# OSO-FEAL-A1-00.net
KiCad netlist of a schematic drawn in EAGLE
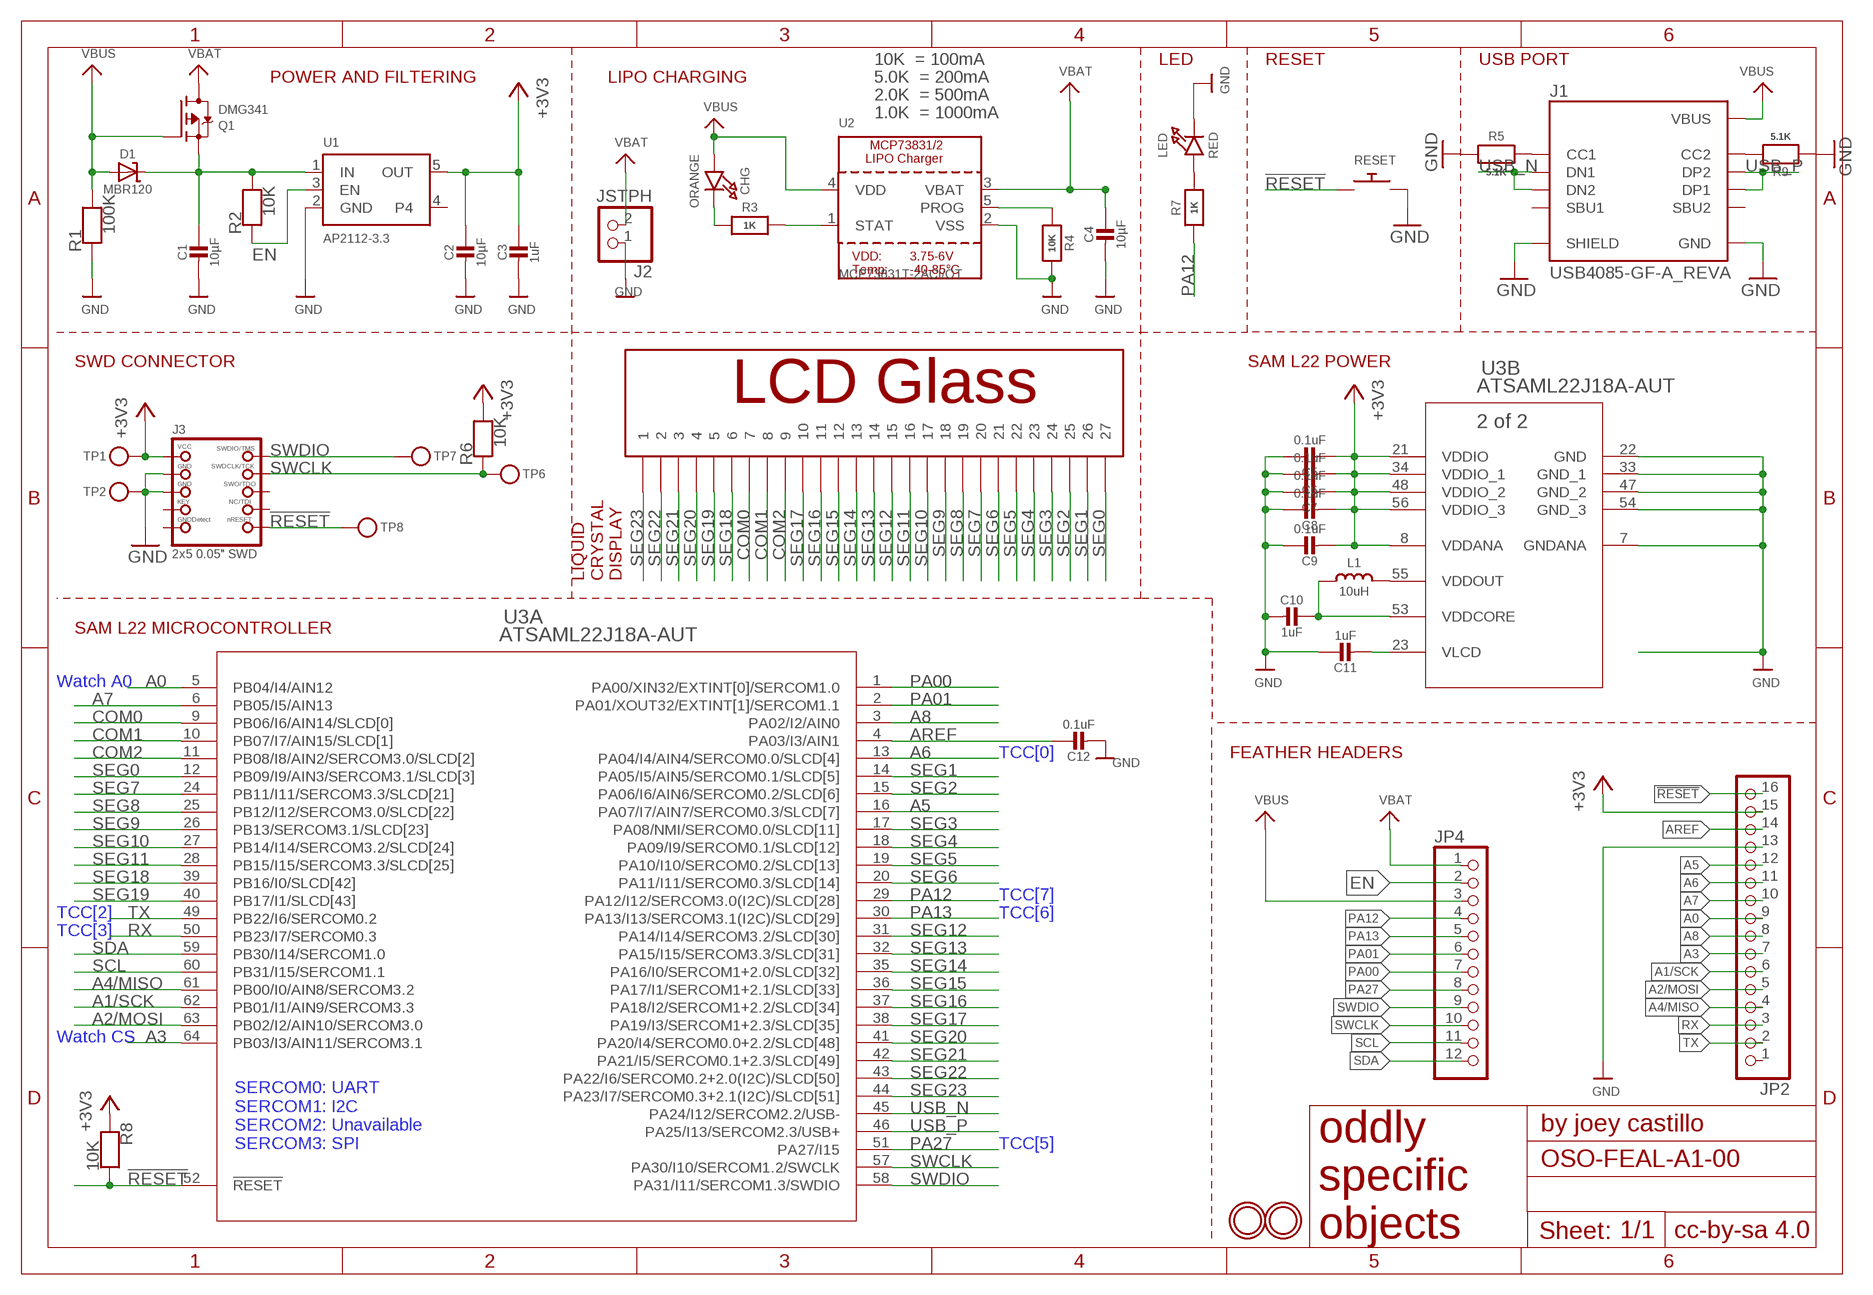
[diagram p0: schematic, sheet 1]

(export (version "E")
  (design (tool "Eeschema 10.0.6"))
  (components
    (comp (ref "C1")
      (value "10µF")
      (footprint "eagle-import:_1206")
      (libsource (lib "eagle-import") (part "CAP_CERAMIC_1206"))
    )
    (comp (ref "C2")
      (value "10µF")
      (footprint "eagle-import:_1206")
      (libsource (lib "eagle-import") (part "CAP_CERAMIC_1206"))
    )
    (comp (ref "C3")
      (value "1uF")
      (footprint "eagle-import:_1206")
      (libsource (lib "eagle-import") (part "CAP_CERAMIC_1206"))
    )
    (comp (ref "C4")
      (value "10µF")
      (footprint "eagle-import:_1206")
      (libsource (lib "eagle-import") (part "CAP_CERAMIC_1206"))
    )
    (comp (ref "C5")
      (value "0.1uF")
      (footprint "eagle-import:0603-NO")
      (libsource (lib "eagle-import") (part "CAP_CERAMIC0603_NO"))
    )
    (comp (ref "C6")
      (value "0.1uF")
      (footprint "eagle-import:0603-NO")
      (libsource (lib "eagle-import") (part "CAP_CERAMIC0603_NO"))
    )
    (comp (ref "C7")
      (value "0.1uF")
      (footprint "eagle-import:0603-NO")
      (libsource (lib "eagle-import") (part "CAP_CERAMIC0603_NO"))
    )
    (comp (ref "C8")
      (value "0.1uF")
      (footprint "eagle-import:0603-NO")
      (libsource (lib "eagle-import") (part "CAP_CERAMIC0603_NO"))
    )
    (comp (ref "C9")
      (value "0.1uF")
      (footprint "eagle-import:0603-NO")
      (libsource (lib "eagle-import") (part "CAP_CERAMIC0603_NO"))
    )
    (comp (ref "C10")
      (value "1uF")
      (footprint "eagle-import:_1206")
      (libsource (lib "eagle-import") (part "CAP_CERAMIC_1206"))
    )
    (comp (ref "C11")
      (value "1uF")
      (footprint "eagle-import:_1206")
      (libsource (lib "eagle-import") (part "CAP_CERAMIC_1206"))
    )
    (comp (ref "C12")
      (value "0.1uF")
      (footprint "eagle-import:0603-NO")
      (libsource (lib "eagle-import") (part "CAP_CERAMIC0603_NO"))
    )
    (comp (ref "CHG")
      (value "ORANGE")
      (footprint "eagle-import:CHIPLED_0805_NOOUTLINE")
      (libsource (lib "eagle-import") (part "LED0805_NOOUTLINE"))
    )
    (comp (ref "D1")
      (value "MBR120")
      (footprint "eagle-import:SOD-123")
      (libsource (lib "eagle-import") (part "DIODE-SCHOTTKYSOD-123"))
    )
    (comp (ref "J1")
      (value "USB4085-GF-A_REVA")
      (footprint "eagle-import:GCT_USB4085-GF-A_REVA")
      (fields
        (field (name "DIGI-KEY_PART_NUMBER") "2073-USB4085-GF-ACT-ND")
        (field (name "MF") "Global Connector Technology")
        (field (name "MP") "USB4085-GF-A")
      )
      (libsource (lib "eagle-import") (part "USB4085-GF-A_REVA"))
    )
    (comp (ref "J2")
      (value "JSTPH")
      (footprint "eagle-import:JSTPH2")
      (libsource (lib "eagle-import") (part "CON_JST_PH_2PIN"))
    )
    (comp (ref "J3")
      (value "2x5 0.05\" SWD")
      (footprint "eagle-import:2X05_1.27MM_BOX_NOPOSTS")
      (libsource (lib "eagle-import") (part "JTAG-CORTEXBOX"))
    )
    (comp (ref "JP2")
      (value "HEADER-1X16_MIN")
      (footprint "eagle-import:1X16_ROUND_MIN")
      (libsource (lib "eagle-import") (part "HEADER-1X16_MIN"))
    )
    (comp (ref "JP4")
      (value "HEADER-1X12_MIN")
      (footprint "eagle-import:1X12_ROUND_MIN")
      (libsource (lib "eagle-import") (part "HEADER-1X12_MIN"))
    )
    (comp (ref "L1")
      (value "10uH")
      (footprint "eagle-import:MICROBUILDER__0805MP")
      (libsource (lib "eagle-import") (part "MICROBUILDER_INDUCTOR_0805MP"))
    )
    (comp (ref "LED")
      (value "RED")
      (footprint "eagle-import:CHIPLED_0805_NOOUTLINE")
      (libsource (lib "eagle-import") (part "LED0805_NOOUTLINE"))
    )
    (comp (ref "Q1")
      (value "DMG341")
      (footprint "eagle-import:SOT23-R")
      (libsource (lib "eagle-import") (part "MOSFET-P"))
    )
    (comp (ref "R1")
      (value "100K")
      (footprint "eagle-import:0603-NO")
      (libsource (lib "eagle-import") (part "RESISTOR_0603_NOOUT"))
    )
    (comp (ref "R2")
      (value "10K")
      (footprint "eagle-import:0603-NO")
      (libsource (lib "eagle-import") (part "RESISTOR_0603_NOOUT"))
    )
    (comp (ref "R3")
      (value "1K")
      (footprint "eagle-import:0603-NO")
      (libsource (lib "eagle-import") (part "RESISTOR_0603_NOOUT"))
    )
    (comp (ref "R4")
      (value "10K")
      (footprint "eagle-import:0603-NO")
      (libsource (lib "eagle-import") (part "RESISTOR_0603_NOOUT"))
    )
    (comp (ref "R5")
      (value "5.1K")
      (footprint "eagle-import:0603-NO")
      (libsource (lib "eagle-import") (part "RESISTOR_0603_NOOUT"))
    )
    (comp (ref "R6")
      (value "10K")
      (footprint "eagle-import:0603-NO")
      (libsource (lib "eagle-import") (part "RESISTOR_0603_NOOUT"))
    )
    (comp (ref "R7")
      (value "1K")
      (footprint "eagle-import:0603-NO")
      (libsource (lib "eagle-import") (part "RESISTOR_0603_NOOUT"))
    )
    (comp (ref "R8")
      (value "10K")
      (footprint "eagle-import:0603-NO")
      (libsource (lib "eagle-import") (part "RESISTOR_0603_NOOUT"))
    )
    (comp (ref "R9")
      (value "5.1K")
      (footprint "eagle-import:0603-NO")
      (libsource (lib "eagle-import") (part "RESISTOR_0603_NOOUT"))
    )
    (comp (ref "RESET")
      (value "SWITCH_PUSHBUTTON_3.5X6MM")
      (footprint "eagle-import:TACTILE_3X6MM")
      (libsource (lib "eagle-import") (part "SWITCH_PUSHBUTTON_3.5X6MM"))
    )
    (comp (ref "TP1")
      (value "TESTPOINTROUND2MMNO")
      (footprint "eagle-import:TESTPOINT_ROUND_2MM_NO")
      (libsource (lib "eagle-import") (part "TESTPOINTROUND2MMNO"))
    )
    (comp (ref "TP2")
      (value "TESTPOINTROUND2MMNO")
      (footprint "eagle-import:TESTPOINT_ROUND_2MM_NO")
      (libsource (lib "eagle-import") (part "TESTPOINTROUND2MMNO"))
    )
    (comp (ref "TP6")
      (value "TESTPOINTROUND2MMNO")
      (footprint "eagle-import:TESTPOINT_ROUND_2MM_NO")
      (libsource (lib "eagle-import") (part "TESTPOINTROUND2MMNO"))
    )
    (comp (ref "TP7")
      (value "TESTPOINTROUND2MMNO")
      (footprint "eagle-import:TESTPOINT_ROUND_2MM_NO")
      (libsource (lib "eagle-import") (part "TESTPOINTROUND2MMNO"))
    )
    (comp (ref "TP8")
      (value "TESTPOINTROUND2MMNO")
      (footprint "eagle-import:TESTPOINT_ROUND_2MM_NO")
      (libsource (lib "eagle-import") (part "TESTPOINTROUND2MMNO"))
    )
    (comp (ref "U$4")
      (value "LCD_FEATHER_DISPLAY")
      (footprint "eagle-import:LCD_FEATHER_DISPLAY")
      (libsource (lib "eagle-import") (part "LCD_FEATHER_DISPLAY"))
    )
    (comp (ref "U$31")
      (value "MOUNTINGHOLE2.5")
      (footprint "eagle-import:MOUNTINGHOLE_2.5_PLATED")
      (libsource (lib "eagle-import") (part "MOUNTINGHOLE2.5"))
    )
    (comp (ref "U$32")
      (value "MOUNTINGHOLE2.5")
      (footprint "eagle-import:MOUNTINGHOLE_2.5_PLATED")
      (libsource (lib "eagle-import") (part "MOUNTINGHOLE2.5"))
    )
    (comp (ref "U1")
      (value "AP2112-3.3")
      (footprint "eagle-import:SOT23-5")
      (libsource (lib "eagle-import") (part "VREG_SOT23-5"))
    )
    (comp (ref "U2")
      (value "MCP73831T-2ACI/OT")
      (footprint "eagle-import:SOT23-5")
      (libsource (lib "eagle-import") (part "MCP73831/2"))
    )
    (comp (ref "U3")
      (value "ATSAML22J18A-AUT")
      (footprint "eagle-import:TQFP64_10X10MC_MCH-L")
      (libsource (lib "eagle-import") (part "ATSAML22J18A-AUT"))
    )
  )
  (nets
    (net (code "1") (name "+3V3") (class "Default")
      (node (ref "C2") (pin "1") (pinfunction "1_1") (pintype "passive"))
      (node (ref "C3") (pin "1") (pinfunction "1_1") (pintype "passive"))
      (node (ref "C5") (pin "2") (pinfunction "2_2") (pintype "passive"))
      (node (ref "C6") (pin "2") (pinfunction "2_2") (pintype "passive"))
      (node (ref "C7") (pin "2") (pinfunction "2_2") (pintype "passive"))
      (node (ref "C8") (pin "2") (pinfunction "2_2") (pintype "passive"))
      (node (ref "C9") (pin "2") (pinfunction "2_2") (pintype "passive"))
      (node (ref "J3") (pin "1") (pinfunction "VCC_1") (pintype "power_in"))
      (node (ref "JP2") (pin "15") (pinfunction "15_15") (pintype "passive"))
      (node (ref "R6") (pin "2") (pinfunction "2_2") (pintype "passive"))
      (node (ref "R8") (pin "1") (pinfunction "1_1") (pintype "passive"))
      (node (ref "TP1") (pin "P$1") (pinfunction "P$1_P$1") (pintype "bidirectional"))
      (node (ref "U1") (pin "5") (pinfunction "OUT_5") (pintype "power_in"))
      (node (ref "U3") (pin "21") (pinfunction "VDDIO_21") (pintype "power_in"))
      (node (ref "U3") (pin "34") (pinfunction "VDDIO_1_34") (pintype "power_in"))
      (node (ref "U3") (pin "48") (pinfunction "VDDIO_2_48") (pintype "power_in"))
      (node (ref "U3") (pin "56") (pinfunction "VDDIO_3_56") (pintype "power_in"))
      (node (ref "U3") (pin "8") (pinfunction "VDDANA_8") (pintype "power_in"))
    )
    (net (code "2") (name "/COM0") (class "Default")
      (node (ref "U$4") (pin "P$7") (pinfunction "7_P$7") (pintype "input"))
      (node (ref "U3") (pin "9") (pinfunction "PB06/I6/AIN14/SLCD[0]_9") (pintype "bidirectional"))
    )
    (net (code "3") (name "/COM1") (class "Default")
      (node (ref "U$4") (pin "P$8") (pinfunction "8_P$8") (pintype "input"))
      (node (ref "U3") (pin "10") (pinfunction "PB07/I7/AIN15/SLCD[1]_10") (pintype "bidirectional"))
    )
    (net (code "4") (name "/COM2") (class "Default")
      (node (ref "U$4") (pin "P$9") (pinfunction "9_P$9") (pintype "input"))
      (node (ref "U3") (pin "11") (pinfunction "PB08/I8/AIN2/SERCOM3.0/SLCD[2]_11") (pintype "bidirectional"))
    )
    (net (code "5") (name "/SEG0") (class "Default")
      (node (ref "U$4") (pin "P$27") (pinfunction "27_P$27") (pintype "input"))
      (node (ref "U3") (pin "12") (pinfunction "PB09/I9/AIN3/SERCOM3.1/SLCD[3]_12") (pintype "bidirectional"))
    )
    (net (code "6") (name "/SEG1") (class "Default")
      (node (ref "U$4") (pin "P$26") (pinfunction "26_P$26") (pintype "input"))
      (node (ref "U3") (pin "14") (pinfunction "PA05/I5/AIN5/SERCOM0.1/SLCD[5]_14") (pintype "bidirectional"))
    )
    (net (code "7") (name "/SEG2") (class "Default")
      (node (ref "U$4") (pin "P$25") (pinfunction "25_P$25") (pintype "input"))
      (node (ref "U3") (pin "15") (pinfunction "PA06/I6/AIN6/SERCOM0.2/SLCD[6]_15") (pintype "bidirectional"))
    )
    (net (code "8") (name "/SEG3") (class "Default")
      (node (ref "U$4") (pin "P$24") (pinfunction "24_P$24") (pintype "input"))
      (node (ref "U3") (pin "17") (pinfunction "PA08/NMI/SERCOM0.0/SLCD[11]_17") (pintype "bidirectional"))
    )
    (net (code "9") (name "/SEG4") (class "Default")
      (node (ref "U$4") (pin "P$23") (pinfunction "23_P$23") (pintype "input"))
      (node (ref "U3") (pin "18") (pinfunction "PA09/I9/SERCOM0.1/SLCD[12]_18") (pintype "bidirectional"))
    )
    (net (code "10") (name "/SEG5") (class "Default")
      (node (ref "U$4") (pin "P$22") (pinfunction "22_P$22") (pintype "input"))
      (node (ref "U3") (pin "19") (pinfunction "PA10/I10/SERCOM0.2/SLCD[13]_19") (pintype "bidirectional"))
    )
    (net (code "11") (name "/SEG6") (class "Default")
      (node (ref "U$4") (pin "P$21") (pinfunction "21_P$21") (pintype "input"))
      (node (ref "U3") (pin "20") (pinfunction "PA11/I11/SERCOM0.3/SLCD[14]_20") (pintype "bidirectional"))
    )
    (net (code "12") (name "/SEG7") (class "Default")
      (node (ref "U$4") (pin "P$20") (pinfunction "20_P$20") (pintype "input"))
      (node (ref "U3") (pin "24") (pinfunction "PB11/I11/SERCOM3.3/SLCD[21]_24") (pintype "bidirectional"))
    )
    (net (code "13") (name "/SEG8") (class "Default")
      (node (ref "U$4") (pin "P$19") (pinfunction "19_P$19") (pintype "input"))
      (node (ref "U3") (pin "25") (pinfunction "PB12/I12/SERCOM3.0/SLCD[22]_25") (pintype "bidirectional"))
    )
    (net (code "14") (name "/SEG9") (class "Default")
      (node (ref "U$4") (pin "P$18") (pinfunction "18_P$18") (pintype "input"))
      (node (ref "U3") (pin "26") (pinfunction "PB13/SERCOM3.1/SLCD[23]_26") (pintype "bidirectional"))
    )
    (net (code "15") (name "/SEG10") (class "Default")
      (node (ref "U$4") (pin "P$17") (pinfunction "17_P$17") (pintype "input"))
      (node (ref "U3") (pin "27") (pinfunction "PB14/I14/SERCOM3.2/SLCD[24]_27") (pintype "bidirectional"))
    )
    (net (code "16") (name "/SEG11") (class "Default")
      (node (ref "U$4") (pin "P$16") (pinfunction "16_P$16") (pintype "input"))
      (node (ref "U3") (pin "28") (pinfunction "PB15/I15/SERCOM3.3/SLCD[25]_28") (pintype "bidirectional"))
    )
    (net (code "17") (name "/SEG12") (class "Default")
      (node (ref "U$4") (pin "P$15") (pinfunction "15_P$15") (pintype "input"))
      (node (ref "U3") (pin "31") (pinfunction "PA14/I14/SERCOM3.2/SLCD[30]_31") (pintype "bidirectional"))
    )
    (net (code "18") (name "/SEG13") (class "Default")
      (node (ref "U$4") (pin "P$14") (pinfunction "14_P$14") (pintype "input"))
      (node (ref "U3") (pin "32") (pinfunction "PA15/I15/SERCOM3.3/SLCD[31]_32") (pintype "bidirectional"))
    )
    (net (code "19") (name "/SEG14") (class "Default")
      (node (ref "U$4") (pin "P$13") (pinfunction "13_P$13") (pintype "input"))
      (node (ref "U3") (pin "35") (pinfunction "PA16/I0/SERCOM1+2.0/SLCD[32]_35") (pintype "bidirectional"))
    )
    (net (code "20") (name "/SEG15") (class "Default")
      (node (ref "U$4") (pin "P$12") (pinfunction "12_P$12") (pintype "input"))
      (node (ref "U3") (pin "36") (pinfunction "PA17/I1/SERCOM1+2.1/SLCD[33]_36") (pintype "bidirectional"))
    )
    (net (code "21") (name "/SEG16") (class "Default")
      (node (ref "U$4") (pin "P$11") (pinfunction "11_P$11") (pintype "input"))
      (node (ref "U3") (pin "37") (pinfunction "PA18/I2/SERCOM1+2.2/SLCD[34]_37") (pintype "bidirectional"))
    )
    (net (code "22") (name "/SEG17") (class "Default")
      (node (ref "U$4") (pin "P$10") (pinfunction "10_P$10") (pintype "input"))
      (node (ref "U3") (pin "38") (pinfunction "PA19/I3/SERCOM1+2.3/SLCD[35]_38") (pintype "bidirectional"))
    )
    (net (code "23") (name "/SEG18") (class "Default")
      (node (ref "U$4") (pin "P$6") (pinfunction "6_P$6") (pintype "input"))
      (node (ref "U3") (pin "39") (pinfunction "PB16/I0/SLCD[42]_39") (pintype "bidirectional"))
    )
    (net (code "24") (name "/SEG19") (class "Default")
      (node (ref "U$4") (pin "P$5") (pinfunction "5_P$5") (pintype "input"))
      (node (ref "U3") (pin "40") (pinfunction "PB17/I1/SLCD[43]_40") (pintype "bidirectional"))
    )
    (net (code "25") (name "/SEG20") (class "Default")
      (node (ref "U$4") (pin "P$4") (pinfunction "4_P$4") (pintype "input"))
      (node (ref "U3") (pin "41") (pinfunction "PA20/I4/SERCOM0.0+2.2/SLCD[48]_41") (pintype "bidirectional"))
    )
    (net (code "26") (name "/SEG21") (class "Default")
      (node (ref "U$4") (pin "P$3") (pinfunction "3_P$3") (pintype "input"))
      (node (ref "U3") (pin "42") (pinfunction "PA21/I5/SERCOM0.1+2.3/SLCD[49]_42") (pintype "bidirectional"))
    )
    (net (code "27") (name "/SEG22") (class "Default")
      (node (ref "U$4") (pin "P$2") (pinfunction "2_P$2") (pintype "input"))
      (node (ref "U3") (pin "43") (pinfunction "PA22/I6/SERCOM0.2+2.0(I2C)/SLCD[50]_43") (pintype "bidirectional"))
    )
    (net (code "28") (name "/SEG23") (class "Default")
      (node (ref "U$4") (pin "P$1") (pinfunction "1_P$1") (pintype "input"))
      (node (ref "U3") (pin "44") (pinfunction "PA23/I7/SERCOM0.3+2.1(I2C)/SLCD[51]_44") (pintype "bidirectional"))
    )
    (net (code "29") (name "/USB_N") (class "Default")
      (node (ref "J1") (pin "A7") (pinfunction "DN1_A7") (pintype "bidirectional"))
      (node (ref "J1") (pin "B7") (pinfunction "DN2_B7") (pintype "bidirectional"))
      (node (ref "U3") (pin "45") (pinfunction "PA24/I12/SERCOM2.2/USB-_45") (pintype "bidirectional"))
    )
    (net (code "30") (name "/USB_P") (class "Default")
      (node (ref "J1") (pin "A6") (pinfunction "DP1_A6") (pintype "bidirectional"))
      (node (ref "J1") (pin "B6") (pinfunction "DP2_B6") (pintype "bidirectional"))
      (node (ref "U3") (pin "46") (pinfunction "PA25/I13/SERCOM2.3/USB+_46") (pintype "bidirectional"))
    )
    (net (code "31") (name "/~{RESET}") (class "Default")
      (node (ref "J3") (pin "10") (pinfunction "NRESET_10") (pintype "bidirectional"))
      (node (ref "JP2") (pin "16") (pinfunction "16_16") (pintype "passive"))
      (node (ref "R8") (pin "2") (pinfunction "2_2") (pintype "passive"))
      (node (ref "RESET") (pin "P$1") (pinfunction "P$1_P$1") (pintype "passive"))
      (node (ref "TP8") (pin "P$1") (pinfunction "P$1_P$1") (pintype "bidirectional"))
      (node (ref "U3") (pin "52") (pinfunction "~{RESET}_52") (pintype "bidirectional"))
    )
    (net (code "32") (name "A0") (class "Default")
      (node (ref "JP2") (pin "9") (pinfunction "9_9") (pintype "passive"))
      (node (ref "U3") (pin "5") (pinfunction "PB04/I4/AIN12_5") (pintype "bidirectional"))
    )
    (net (code "33") (name "A1{slash}SCK") (class "Default")
      (node (ref "JP2") (pin "6") (pinfunction "6_6") (pintype "passive"))
      (node (ref "U3") (pin "62") (pinfunction "PB01/I1/AIN9/SERCOM3.3_62") (pintype "bidirectional"))
    )
    (net (code "34") (name "A2{slash}MOSI") (class "Default")
      (node (ref "JP2") (pin "5") (pinfunction "5_5") (pintype "passive"))
      (node (ref "U3") (pin "63") (pinfunction "PB02/I2/AIN10/SERCOM3.0_63") (pintype "bidirectional"))
    )
    (net (code "35") (name "A3") (class "Default")
      (node (ref "JP2") (pin "7") (pinfunction "7_7") (pintype "passive"))
      (node (ref "U3") (pin "64") (pinfunction "PB03/I3/AIN11/SERCOM3.1_64") (pintype "bidirectional"))
    )
    (net (code "36") (name "A4{slash}MISO") (class "Default")
      (node (ref "JP2") (pin "4") (pinfunction "4_4") (pintype "passive"))
      (node (ref "U3") (pin "61") (pinfunction "PB00/I0/AIN8/SERCOM3.2_61") (pintype "bidirectional"))
    )
    (net (code "37") (name "A5") (class "Default")
      (node (ref "JP2") (pin "12") (pinfunction "12_12") (pintype "passive"))
      (node (ref "U3") (pin "16") (pinfunction "PA07/I7/AIN7/SERCOM0.3/SLCD[7]_16") (pintype "bidirectional"))
    )
    (net (code "38") (name "A6") (class "Default")
      (node (ref "JP2") (pin "11") (pinfunction "11_11") (pintype "passive"))
      (node (ref "U3") (pin "13") (pinfunction "PA04/I4/AIN4/SERCOM0.0/SLCD[4]_13") (pintype "bidirectional"))
    )
    (net (code "39") (name "A7") (class "Default")
      (node (ref "JP2") (pin "10") (pinfunction "10_10") (pintype "passive"))
      (node (ref "U3") (pin "6") (pinfunction "PB05/I5/AIN13_6") (pintype "bidirectional"))
    )
    (net (code "40") (name "A8") (class "Default")
      (node (ref "JP2") (pin "8") (pinfunction "8_8") (pintype "passive"))
      (node (ref "U3") (pin "3") (pinfunction "PA02/I2/AIN0_3") (pintype "bidirectional"))
    )
    (net (code "41") (name "AREF") (class "Default")
      (node (ref "C12") (pin "1") (pinfunction "1_1") (pintype "passive"))
      (node (ref "JP2") (pin "14") (pinfunction "14_14") (pintype "passive"))
      (node (ref "U3") (pin "4") (pinfunction "PA03/I3/AIN1_4") (pintype "bidirectional"))
    )
    (net (code "42") (name "EN") (class "Default")
      (node (ref "JP4") (pin "2") (pinfunction "2_2") (pintype "passive"))
      (node (ref "R2") (pin "1") (pinfunction "1_1") (pintype "passive"))
      (node (ref "U1") (pin "3") (pinfunction "EN_3") (pintype "input"))
    )
    (net (code "43") (name "GND") (class "Default")
      (node (ref "C1") (pin "2") (pinfunction "2_2") (pintype "passive"))
      (node (ref "C10") (pin "2") (pinfunction "2_2") (pintype "passive"))
      (node (ref "C11") (pin "1") (pinfunction "1_1") (pintype "passive"))
      (node (ref "C12") (pin "2") (pinfunction "2_2") (pintype "passive"))
      (node (ref "C2") (pin "2") (pinfunction "2_2") (pintype "passive"))
      (node (ref "C3") (pin "2") (pinfunction "2_2") (pintype "passive"))
      (node (ref "C4") (pin "2") (pinfunction "2_2") (pintype "passive"))
      (node (ref "C5") (pin "1") (pinfunction "1_1") (pintype "passive"))
      (node (ref "C6") (pin "1") (pinfunction "1_1") (pintype "passive"))
      (node (ref "C7") (pin "1") (pinfunction "1_1") (pintype "passive"))
      (node (ref "C8") (pin "1") (pinfunction "1_1") (pintype "passive"))
      (node (ref "C9") (pin "1") (pinfunction "1_1") (pintype "passive"))
      (node (ref "J1") (pin "A1") (pinfunction "GND_A1") (pintype "passive"))
      (node (ref "J1") (pin "A12") (pinfunction "GND_A12") (pintype "passive"))
      (node (ref "J1") (pin "B1") (pinfunction "GND_B1") (pintype "passive"))
      (node (ref "J1") (pin "B12") (pinfunction "GND_B12") (pintype "passive"))
      (node (ref "J1") (pin "P1") (pinfunction "SHIELD_P1") (pintype "passive"))
      (node (ref "J1") (pin "P2") (pinfunction "SHIELD_P2") (pintype "passive"))
      (node (ref "J1") (pin "P3") (pinfunction "SHIELD_P3") (pintype "passive"))
      (node (ref "J1") (pin "P4") (pinfunction "SHIELD_P4") (pintype "passive"))
      (node (ref "J2") (pin "1") (pinfunction "1_1") (pintype "passive"))
      (node (ref "J3") (pin "3") (pinfunction "GND_3") (pintype "power_in"))
      (node (ref "J3") (pin "5") (pinfunction "GND_5") (pintype "power_in"))
      (node (ref "JP2") (pin "13") (pinfunction "13_13") (pintype "passive"))
      (node (ref "LED") (pin "C") (pinfunction "C_C") (pintype "passive"))
      (node (ref "R1") (pin "1") (pinfunction "1_1") (pintype "passive"))
      (node (ref "R4") (pin "2") (pinfunction "2_2") (pintype "passive"))
      (node (ref "R5") (pin "1") (pinfunction "1_1") (pintype "passive"))
      (node (ref "R9") (pin "2") (pinfunction "2_2") (pintype "passive"))
      (node (ref "RESET") (pin "P$2") (pinfunction "P$2_P$2") (pintype "passive"))
      (node (ref "TP2") (pin "P$1") (pinfunction "P$1_P$1") (pintype "bidirectional"))
      (node (ref "U1") (pin "2") (pinfunction "GND_2") (pintype "power_in"))
      (node (ref "U2") (pin "2") (pinfunction "VSS_2") (pintype "power_in"))
      (node (ref "U3") (pin "22") (pinfunction "GND_22") (pintype "passive"))
      (node (ref "U3") (pin "33") (pinfunction "GND_1_33") (pintype "passive"))
      (node (ref "U3") (pin "47") (pinfunction "GND_2_47") (pintype "passive"))
      (node (ref "U3") (pin "54") (pinfunction "GND_3_54") (pintype "passive"))
      (node (ref "U3") (pin "7") (pinfunction "GNDANA_7") (pintype "passive"))
    )
    (net (code "44") (name "Net-(CHG-PadC)") (class "Default")
      (node (ref "CHG") (pin "C") (pinfunction "C_C") (pintype "passive"))
      (node (ref "R3") (pin "1") (pinfunction "1_1") (pintype "passive"))
    )
    (net (code "45") (name "Net-(J1-CC1)") (class "Default")
      (node (ref "J1") (pin "A5") (pinfunction "CC1_A5") (pintype "bidirectional"))
      (node (ref "R5") (pin "2") (pinfunction "2_2") (pintype "passive"))
    )
    (net (code "46") (name "Net-(J1-CC2)") (class "Default")
      (node (ref "J1") (pin "B5") (pinfunction "CC2_B5") (pintype "bidirectional"))
      (node (ref "R9") (pin "1") (pinfunction "1_1") (pintype "passive"))
    )
    (net (code "47") (name "Net-(LED-PadA)") (class "Default")
      (node (ref "LED") (pin "A") (pinfunction "A_A") (pintype "passive"))
      (node (ref "R7") (pin "2") (pinfunction "2_2") (pintype "passive"))
    )
    (net (code "48") (name "Net-(Q1-S)") (class "Default")
      (node (ref "C1") (pin "1") (pinfunction "1_1") (pintype "passive"))
      (node (ref "D1") (pin "C") (pinfunction "C_C") (pintype "passive"))
      (node (ref "Q1") (pin "2") (pinfunction "S_2") (pintype "passive"))
      (node (ref "R2") (pin "2") (pinfunction "2_2") (pintype "passive"))
      (node (ref "U1") (pin "1") (pinfunction "IN_1") (pintype "power_in"))
    )
    (net (code "49") (name "Net-(U2-PROG)") (class "Default")
      (node (ref "R4") (pin "1") (pinfunction "1_1") (pintype "passive"))
      (node (ref "U2") (pin "5") (pinfunction "PROG_5") (pintype "input"))
    )
    (net (code "50") (name "Net-(U2-STAT)") (class "Default")
      (node (ref "R3") (pin "2") (pinfunction "2_2") (pintype "passive"))
      (node (ref "U2") (pin "1") (pinfunction "STAT_1") (pintype "output"))
    )
    (net (code "51") (name "Net-(U3B-VDDCORE)") (class "Default")
      (node (ref "C10") (pin "1") (pinfunction "1_1") (pintype "passive"))
      (node (ref "L1") (pin "1") (pinfunction "1_1") (pintype "passive"))
      (node (ref "U3") (pin "53") (pinfunction "VDDCORE_53") (pintype "power_in"))
    )
    (net (code "52") (name "Net-(U3B-VDDOUT)") (class "Default")
      (node (ref "L1") (pin "2") (pinfunction "2_2") (pintype "passive"))
      (node (ref "U3") (pin "55") (pinfunction "VDDOUT_55") (pintype "output"))
    )
    (net (code "53") (name "Net-(U3B-VLCD)") (class "Default")
      (node (ref "C11") (pin "2") (pinfunction "2_2") (pintype "passive"))
      (node (ref "U3") (pin "23") (pinfunction "VLCD_23") (pintype "passive"))
    )
    (net (code "54") (name "PA00") (class "Default")
      (node (ref "JP4") (pin "7") (pinfunction "7_7") (pintype "passive"))
      (node (ref "U3") (pin "1") (pinfunction "PA00/XIN32/EXTINT[0]/SERCOM1.0_1") (pintype "bidirectional"))
    )
    (net (code "55") (name "PA01") (class "Default")
      (node (ref "JP4") (pin "6") (pinfunction "6_6") (pintype "passive"))
      (node (ref "U3") (pin "2") (pinfunction "PA01/XOUT32/EXTINT[1]/SERCOM1.1_2") (pintype "bidirectional"))
    )
    (net (code "56") (name "PA12") (class "Default")
      (node (ref "JP4") (pin "4") (pinfunction "4_4") (pintype "passive"))
      (node (ref "R7") (pin "1") (pinfunction "1_1") (pintype "passive"))
      (node (ref "U3") (pin "29") (pinfunction "PA12/I12/SERCOM3.0(I2C)/SLCD[28]_29") (pintype "bidirectional"))
    )
    (net (code "57") (name "PA13") (class "Default")
      (node (ref "JP4") (pin "5") (pinfunction "5_5") (pintype "passive"))
      (node (ref "U3") (pin "30") (pinfunction "PA13/I13/SERCOM3.1(I2C)/SLCD[29]_30") (pintype "bidirectional"))
    )
    (net (code "58") (name "PA27") (class "Default")
      (node (ref "JP4") (pin "8") (pinfunction "8_8") (pintype "passive"))
      (node (ref "U3") (pin "51") (pinfunction "PA27/I15_51") (pintype "bidirectional"))
    )
    (net (code "59") (name "RX") (class "Default")
      (node (ref "JP2") (pin "3") (pinfunction "3_3") (pintype "passive"))
      (node (ref "U3") (pin "50") (pinfunction "PB23/I7/SERCOM0.3_50") (pintype "bidirectional"))
    )
    (net (code "60") (name "SCL") (class "Default")
      (node (ref "JP4") (pin "11") (pinfunction "11_11") (pintype "passive"))
      (node (ref "U3") (pin "60") (pinfunction "PB31/I15/SERCOM1.1_60") (pintype "bidirectional"))
    )
    (net (code "61") (name "SDA") (class "Default")
      (node (ref "JP4") (pin "12") (pinfunction "12_12") (pintype "passive"))
      (node (ref "U3") (pin "59") (pinfunction "PB30/I14/SERCOM1.0_59") (pintype "bidirectional"))
    )
    (net (code "62") (name "SWCLK") (class "Default")
      (node (ref "J3") (pin "4") (pinfunction "SWDCLK_4") (pintype "bidirectional"))
      (node (ref "JP4") (pin "10") (pinfunction "10_10") (pintype "passive"))
      (node (ref "R6") (pin "1") (pinfunction "1_1") (pintype "passive"))
      (node (ref "TP6") (pin "P$1") (pinfunction "P$1_P$1") (pintype "bidirectional"))
      (node (ref "U3") (pin "57") (pinfunction "PA30/I10/SERCOM1.2/SWCLK_57") (pintype "bidirectional"))
    )
    (net (code "63") (name "SWDIO") (class "Default")
      (node (ref "J3") (pin "2") (pinfunction "SWDIO_2") (pintype "bidirectional"))
      (node (ref "JP4") (pin "9") (pinfunction "9_9") (pintype "passive"))
      (node (ref "TP7") (pin "P$1") (pinfunction "P$1_P$1") (pintype "bidirectional"))
      (node (ref "U3") (pin "58") (pinfunction "PA31/I11/SERCOM1.3/SWDIO_58") (pintype "bidirectional"))
    )
    (net (code "64") (name "TX") (class "Default")
      (node (ref "JP2") (pin "2") (pinfunction "2_2") (pintype "passive"))
      (node (ref "U3") (pin "49") (pinfunction "PB22/I6/SERCOM0.2_49") (pintype "bidirectional"))
    )
    (net (code "65") (name "VBAT") (class "Default")
      (node (ref "C4") (pin "1") (pinfunction "1_1") (pintype "passive"))
      (node (ref "J2") (pin "2") (pinfunction "2_2") (pintype "passive"))
      (node (ref "JP4") (pin "1") (pinfunction "1_1") (pintype "passive"))
      (node (ref "Q1") (pin "3") (pinfunction "D_3") (pintype "passive"))
      (node (ref "U2") (pin "3") (pinfunction "VBAT_3") (pintype "power_in"))
    )
    (net (code "66") (name "VBUS") (class "Default")
      (node (ref "CHG") (pin "A") (pinfunction "A_A") (pintype "passive"))
      (node (ref "D1") (pin "A") (pinfunction "A_A") (pintype "passive"))
      (node (ref "J1") (pin "A4") (pinfunction "VBUS_A4") (pintype "power_in"))
      (node (ref "J1") (pin "A9") (pinfunction "VBUS_A9") (pintype "power_in"))
      (node (ref "J1") (pin "B4") (pinfunction "VBUS_B4") (pintype "power_in"))
      (node (ref "J1") (pin "B9") (pinfunction "VBUS_B9") (pintype "power_in"))
      (node (ref "JP4") (pin "3") (pinfunction "3_3") (pintype "passive"))
      (node (ref "Q1") (pin "1") (pinfunction "G_1") (pintype "passive"))
      (node (ref "R1") (pin "2") (pinfunction "2_2") (pintype "passive"))
      (node (ref "U2") (pin "4") (pinfunction "VDD_4") (pintype "power_in"))
    )
    (net (code "67") (name "unconnected-(J1-SBU1-PadA8)") (class "Default")
      (node (ref "J1") (pin "A8") (pinfunction "SBU1_A8") (pintype "bidirectional"))
    )
    (net (code "68") (name "unconnected-(J1-SBU2-PadB8)") (class "Default")
      (node (ref "J1") (pin "B8") (pinfunction "SBU2_B8") (pintype "bidirectional"))
    )
    (net (code "69") (name "unconnected-(J3-GNDDETECT-Pad9)") (class "Default")
      (node (ref "J3") (pin "9") (pinfunction "GNDDETECT_9") (pintype "bidirectional"))
    )
    (net (code "70") (name "unconnected-(J3-KEY-Pad7)") (class "Default")
      (node (ref "J3") (pin "7") (pinfunction "KEY_7") (pintype "bidirectional"))
    )
    (net (code "71") (name "unconnected-(J3-SWO-Pad6)") (class "Default")
      (node (ref "J3") (pin "6") (pinfunction "SWO_6") (pintype "bidirectional"))
    )
    (net (code "72") (name "unconnected-(J3-TDI-Pad8)") (class "Default")
      (node (ref "J3") (pin "8") (pinfunction "TDI_8") (pintype "bidirectional"))
    )
    (net (code "73") (name "unconnected-(JP2-Pad1)") (class "Default")
      (node (ref "JP2") (pin "1") (pinfunction "1_1") (pintype "passive"))
    )
    (net (code "74") (name "unconnected-(U1-P4-Pad4)") (class "Default")
      (node (ref "U1") (pin "4") (pinfunction "P4_4") (pintype "bidirectional"))
    )
  )
)
